# leds_vaga.net
KiCad netlist of a schematic drawn in Altium Designer
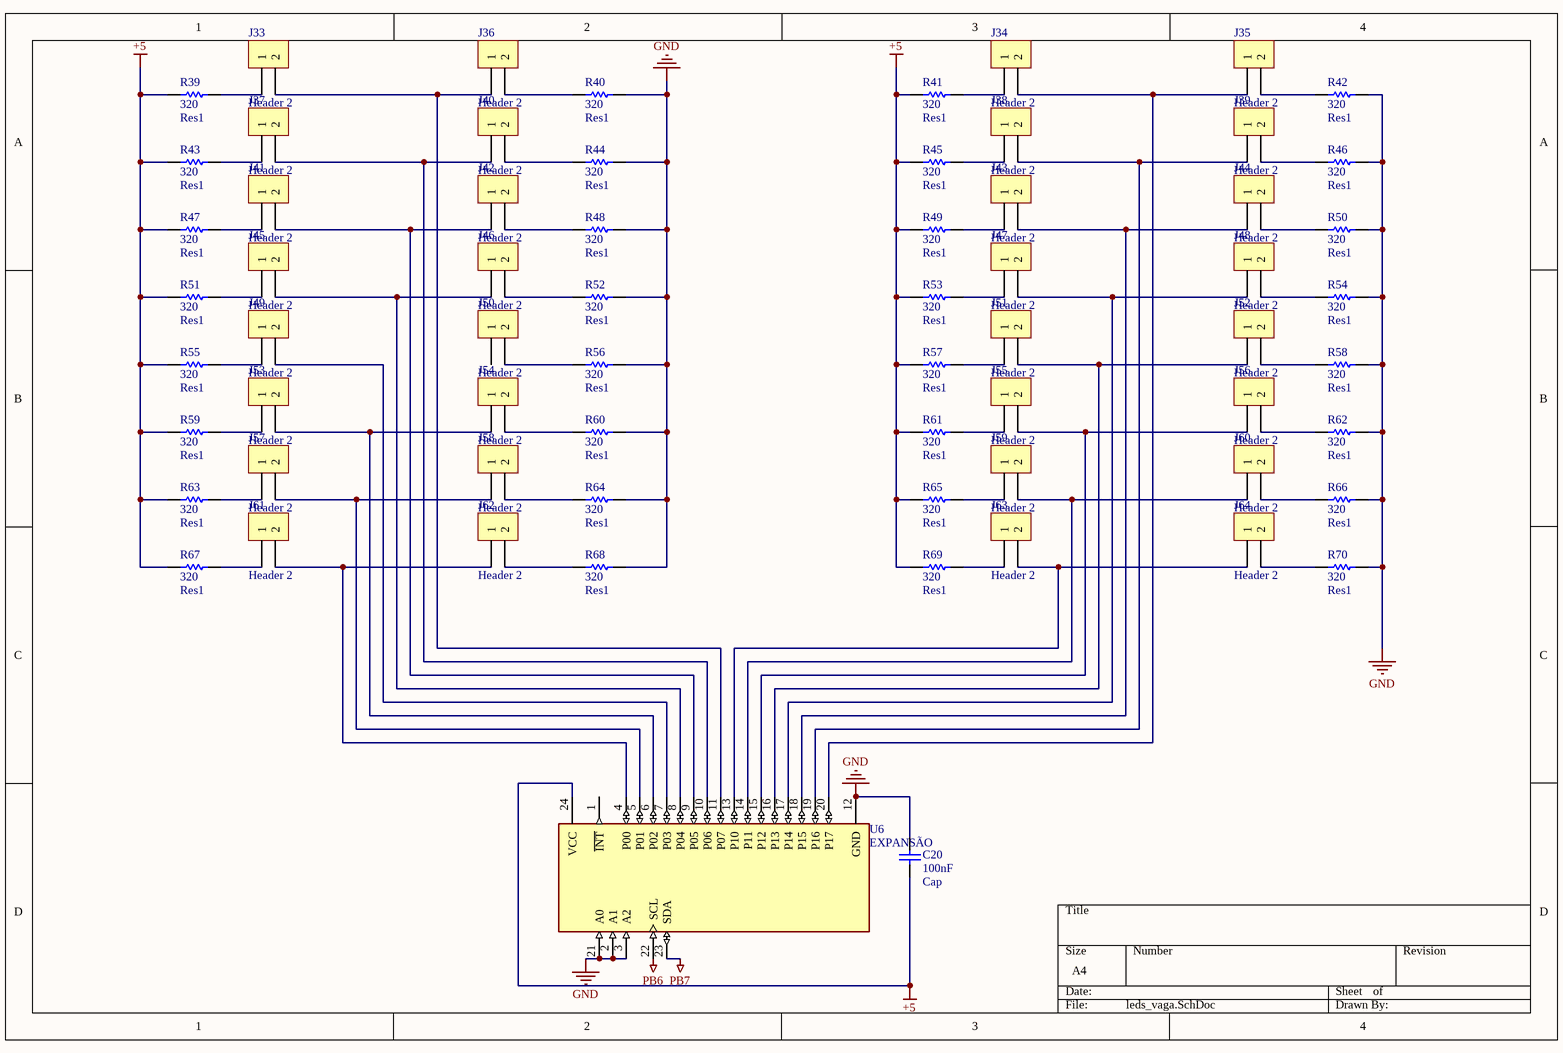
[diagram p0: leds_vaga.SchDoc]

(export (version "E")
  (design (tool "Eeschema 10.0.6"))
  (components
    (comp (ref "C20")
      (value "Cap")
      (footprint "lib_footprint_projeto:CAP100N")
      (description "Capacitor")
      (fields (field (name "ALTIUM_VALUE") "100nF") (field (name "PUBLISHER") "Altium Limited"))
      (libsource (lib "Miscellaneous Devices") (part "Cap"))
    )
    (comp (ref "J33")
      (value "Header 2")
      (footprint "lib_footprint_projeto:Header_KK_2vias")
      (description "Conn KK 2 vias")
      (fields (field (name "PUBLISHER") "Altium Limited"))
      (libsource (lib "projeto_pi_3b") (part "Header 2"))
    )
    (comp (ref "J34")
      (value "Header 2")
      (footprint "lib_footprint_projeto:Header_KK_2vias")
      (description "Conn KK 2 vias")
      (fields (field (name "PUBLISHER") "Altium Limited"))
      (libsource (lib "projeto_pi_3b") (part "Header 2"))
    )
    (comp (ref "J35")
      (value "Header 2")
      (footprint "lib_footprint_projeto:Header_KK_2vias")
      (description "Conn KK 2 vias")
      (fields (field (name "PUBLISHER") "Altium Limited"))
      (libsource (lib "projeto_pi_3b") (part "Header 2"))
    )
    (comp (ref "J36")
      (value "Header 2")
      (footprint "lib_footprint_projeto:Header_KK_2vias")
      (description "Conn KK 2 vias")
      (fields (field (name "PUBLISHER") "Altium Limited"))
      (libsource (lib "projeto_pi_3b") (part "Header 2"))
    )
    (comp (ref "J37")
      (value "Header 2")
      (footprint "lib_footprint_projeto:Header_KK_2vias")
      (description "Conn KK 2 vias")
      (fields (field (name "PUBLISHER") "Altium Limited"))
      (libsource (lib "projeto_pi_3b") (part "Header 2"))
    )
    (comp (ref "J38")
      (value "Header 2")
      (footprint "lib_footprint_projeto:Header_KK_2vias")
      (description "Conn KK 2 vias")
      (fields (field (name "PUBLISHER") "Altium Limited"))
      (libsource (lib "projeto_pi_3b") (part "Header 2"))
    )
    (comp (ref "J39")
      (value "Header 2")
      (footprint "lib_footprint_projeto:Header_KK_2vias")
      (description "Conn KK 2 vias")
      (fields (field (name "PUBLISHER") "Altium Limited"))
      (libsource (lib "projeto_pi_3b") (part "Header 2"))
    )
    (comp (ref "J40")
      (value "Header 2")
      (footprint "Header_KK_2vias")
      (description "Conn KK 2 vias")
      (fields (field (name "PUBLISHER") "Altium Limited"))
      (libsource (lib "projeto_pi_3b") (part "Header 2"))
    )
    (comp (ref "J41")
      (value "Header 2")
      (footprint "lib_footprint_projeto:Header_KK_2vias")
      (description "Conn KK 2 vias")
      (fields (field (name "PUBLISHER") "Altium Limited"))
      (libsource (lib "projeto_pi_3b") (part "Header 2"))
    )
    (comp (ref "J42")
      (value "Header 2")
      (footprint "lib_footprint_projeto:Header_KK_2vias")
      (description "Conn KK 2 vias")
      (fields (field (name "PUBLISHER") "Altium Limited"))
      (libsource (lib "projeto_pi_3b") (part "Header 2"))
    )
    (comp (ref "J43")
      (value "Header 2")
      (footprint "lib_footprint_projeto:Header_KK_2vias")
      (description "Conn KK 2 vias")
      (fields (field (name "PUBLISHER") "Altium Limited"))
      (libsource (lib "projeto_pi_3b") (part "Header 2"))
    )
    (comp (ref "J44")
      (value "Header 2")
      (footprint "lib_footprint_projeto:Header_KK_2vias")
      (description "Conn KK 2 vias")
      (fields (field (name "PUBLISHER") "Altium Limited"))
      (libsource (lib "projeto_pi_3b") (part "Header 2"))
    )
    (comp (ref "J45")
      (value "Header 2")
      (footprint "lib_footprint_projeto:Header_KK_2vias")
      (description "Conn KK 2 vias")
      (fields (field (name "PUBLISHER") "Altium Limited"))
      (libsource (lib "projeto_pi_3b") (part "Header 2"))
    )
    (comp (ref "J46")
      (value "Header 2")
      (footprint "lib_footprint_projeto:Header_KK_2vias")
      (description "Conn KK 2 vias")
      (fields (field (name "PUBLISHER") "Altium Limited"))
      (libsource (lib "projeto_pi_3b") (part "Header 2"))
    )
    (comp (ref "J47")
      (value "Header 2")
      (footprint "lib_footprint_projeto:Header_KK_2vias")
      (description "Conn KK 2 vias")
      (fields (field (name "PUBLISHER") "Altium Limited"))
      (libsource (lib "projeto_pi_3b") (part "Header 2"))
    )
    (comp (ref "J48")
      (value "Header 2")
      (footprint "lib_footprint_projeto:Header_KK_2vias")
      (description "Conn KK 2 vias")
      (fields (field (name "PUBLISHER") "Altium Limited"))
      (libsource (lib "projeto_pi_3b") (part "Header 2"))
    )
    (comp (ref "J49")
      (value "Header 2")
      (footprint "lib_footprint_projeto:Header_KK_2vias")
      (description "Conn KK 2 vias")
      (fields (field (name "PUBLISHER") "Altium Limited"))
      (libsource (lib "projeto_pi_3b") (part "Header 2"))
    )
    (comp (ref "J50")
      (value "Header 2")
      (footprint "lib_footprint_projeto:Header_KK_2vias")
      (description "Conn KK 2 vias")
      (fields (field (name "PUBLISHER") "Altium Limited"))
      (libsource (lib "projeto_pi_3b") (part "Header 2"))
    )
    (comp (ref "J51")
      (value "Header 2")
      (footprint "lib_footprint_projeto:Header_KK_2vias")
      (description "Conn KK 2 vias")
      (fields (field (name "PUBLISHER") "Altium Limited"))
      (libsource (lib "projeto_pi_3b") (part "Header 2"))
    )
    (comp (ref "J52")
      (value "Header 2")
      (footprint "lib_footprint_projeto:Header_KK_2vias")
      (description "Conn KK 2 vias")
      (fields (field (name "PUBLISHER") "Altium Limited"))
      (libsource (lib "projeto_pi_3b") (part "Header 2"))
    )
    (comp (ref "J53")
      (value "Header 2")
      (footprint "lib_footprint_projeto:Header_KK_2vias")
      (description "Conn KK 2 vias")
      (fields (field (name "PUBLISHER") "Altium Limited"))
      (libsource (lib "projeto_pi_3b") (part "Header 2"))
    )
    (comp (ref "J54")
      (value "Header 2")
      (footprint "lib_footprint_projeto:Header_KK_2vias")
      (description "Conn KK 2 vias")
      (fields (field (name "PUBLISHER") "Altium Limited"))
      (libsource (lib "projeto_pi_3b") (part "Header 2"))
    )
    (comp (ref "J55")
      (value "Header 2")
      (footprint "lib_footprint_projeto:Header_KK_2vias")
      (description "Conn KK 2 vias")
      (fields (field (name "PUBLISHER") "Altium Limited"))
      (libsource (lib "projeto_pi_3b") (part "Header 2"))
    )
    (comp (ref "J56")
      (value "Header 2")
      (footprint "lib_footprint_projeto:Header_KK_2vias")
      (description "Conn KK 2 vias")
      (fields (field (name "PUBLISHER") "Altium Limited"))
      (libsource (lib "projeto_pi_3b") (part "Header 2"))
    )
    (comp (ref "J57")
      (value "Header 2")
      (footprint "lib_footprint_projeto:Header_KK_2vias")
      (description "Conn KK 2 vias")
      (fields (field (name "PUBLISHER") "Altium Limited"))
      (libsource (lib "projeto_pi_3b") (part "Header 2"))
    )
    (comp (ref "J58")
      (value "Header 2")
      (footprint "lib_footprint_projeto:Header_KK_2vias")
      (description "Conn KK 2 vias")
      (fields (field (name "PUBLISHER") "Altium Limited"))
      (libsource (lib "projeto_pi_3b") (part "Header 2"))
    )
    (comp (ref "J59")
      (value "Header 2")
      (footprint "lib_footprint_projeto:Header_KK_2vias")
      (description "Conn KK 2 vias")
      (fields (field (name "PUBLISHER") "Altium Limited"))
      (libsource (lib "projeto_pi_3b") (part "Header 2"))
    )
    (comp (ref "J60")
      (value "Header 2")
      (footprint "lib_footprint_projeto:Header_KK_2vias")
      (description "Conn KK 2 vias")
      (fields (field (name "PUBLISHER") "Altium Limited"))
      (libsource (lib "projeto_pi_3b") (part "Header 2"))
    )
    (comp (ref "J61")
      (value "Header 2")
      (footprint "lib_footprint_projeto:Header_KK_2vias")
      (description "Conn KK 2 vias")
      (fields (field (name "PUBLISHER") "Altium Limited"))
      (libsource (lib "projeto_pi_3b") (part "Header 2"))
    )
    (comp (ref "J62")
      (value "Header 2")
      (footprint "lib_footprint_projeto:Header_KK_2vias")
      (description "Conn KK 2 vias")
      (fields (field (name "PUBLISHER") "Altium Limited"))
      (libsource (lib "projeto_pi_3b") (part "Header 2"))
    )
    (comp (ref "J63")
      (value "Header 2")
      (footprint "lib_footprint_projeto:Header_KK_2vias")
      (description "Conn KK 2 vias")
      (fields (field (name "PUBLISHER") "Altium Limited"))
      (libsource (lib "projeto_pi_3b") (part "Header 2"))
    )
    (comp (ref "J64")
      (value "Header 2")
      (footprint "lib_footprint_projeto:Header_KK_2vias")
      (description "Conn KK 2 vias")
      (fields (field (name "PUBLISHER") "Altium Limited"))
      (libsource (lib "projeto_pi_3b") (part "Header 2"))
    )
    (comp (ref "R39")
      (value "Res1")
      (footprint "lib_footprint_projeto:RES320")
      (description "Resistor")
      (fields (field (name "ALTIUM_VALUE") "320") (field (name "PUBLISHER") "Altium Limited"))
      (libsource (lib "Miscellaneous Devices") (part "Res1"))
    )
    (comp (ref "R40")
      (value "Res1")
      (footprint "lib_footprint_projeto:RES320")
      (description "Resistor")
      (fields (field (name "ALTIUM_VALUE") "320") (field (name "PUBLISHER") "Altium Limited"))
      (libsource (lib "Miscellaneous Devices") (part "Res1"))
    )
    (comp (ref "R41")
      (value "Res1")
      (footprint "lib_footprint_projeto:RES320")
      (description "Resistor")
      (fields (field (name "ALTIUM_VALUE") "320") (field (name "PUBLISHER") "Altium Limited"))
      (libsource (lib "Miscellaneous Devices") (part "Res1"))
    )
    (comp (ref "R42")
      (value "Res1")
      (footprint "lib_footprint_projeto:RES320")
      (description "Resistor")
      (fields (field (name "ALTIUM_VALUE") "320") (field (name "PUBLISHER") "Altium Limited"))
      (libsource (lib "Miscellaneous Devices") (part "Res1"))
    )
    (comp (ref "R43")
      (value "Res1")
      (footprint "lib_footprint_projeto:RES320")
      (description "Resistor")
      (fields (field (name "ALTIUM_VALUE") "320") (field (name "PUBLISHER") "Altium Limited"))
      (libsource (lib "Miscellaneous Devices") (part "Res1"))
    )
    (comp (ref "R44")
      (value "Res1")
      (footprint "lib_footprint_projeto:RES320")
      (description "Resistor")
      (fields (field (name "ALTIUM_VALUE") "320") (field (name "PUBLISHER") "Altium Limited"))
      (libsource (lib "Miscellaneous Devices") (part "Res1"))
    )
    (comp (ref "R45")
      (value "Res1")
      (footprint "lib_footprint_projeto:RES320")
      (description "Resistor")
      (fields (field (name "ALTIUM_VALUE") "320") (field (name "PUBLISHER") "Altium Limited"))
      (libsource (lib "Miscellaneous Devices") (part "Res1"))
    )
    (comp (ref "R46")
      (value "Res1")
      (footprint "lib_footprint_projeto:RES320")
      (description "Resistor")
      (fields (field (name "ALTIUM_VALUE") "320") (field (name "PUBLISHER") "Altium Limited"))
      (libsource (lib "Miscellaneous Devices") (part "Res1"))
    )
    (comp (ref "R47")
      (value "Res1")
      (footprint "lib_footprint_projeto:RES320")
      (description "Resistor")
      (fields (field (name "ALTIUM_VALUE") "320") (field (name "PUBLISHER") "Altium Limited"))
      (libsource (lib "Miscellaneous Devices") (part "Res1"))
    )
    (comp (ref "R48")
      (value "Res1")
      (footprint "lib_footprint_projeto:RES320")
      (description "Resistor")
      (fields (field (name "ALTIUM_VALUE") "320") (field (name "PUBLISHER") "Altium Limited"))
      (libsource (lib "Miscellaneous Devices") (part "Res1"))
    )
    (comp (ref "R49")
      (value "Res1")
      (footprint "lib_footprint_projeto:RES320")
      (description "Resistor")
      (fields (field (name "ALTIUM_VALUE") "320") (field (name "PUBLISHER") "Altium Limited"))
      (libsource (lib "Miscellaneous Devices") (part "Res1"))
    )
    (comp (ref "R50")
      (value "Res1")
      (footprint "lib_footprint_projeto:RES320")
      (description "Resistor")
      (fields (field (name "ALTIUM_VALUE") "320") (field (name "PUBLISHER") "Altium Limited"))
      (libsource (lib "Miscellaneous Devices") (part "Res1"))
    )
    (comp (ref "R51")
      (value "Res1")
      (footprint "lib_footprint_projeto:RES320")
      (description "Resistor")
      (fields (field (name "ALTIUM_VALUE") "320") (field (name "PUBLISHER") "Altium Limited"))
      (libsource (lib "Miscellaneous Devices") (part "Res1"))
    )
    (comp (ref "R52")
      (value "Res1")
      (footprint "lib_footprint_projeto:RES320")
      (description "Resistor")
      (fields (field (name "ALTIUM_VALUE") "320") (field (name "PUBLISHER") "Altium Limited"))
      (libsource (lib "Miscellaneous Devices") (part "Res1"))
    )
    (comp (ref "R53")
      (value "Res1")
      (footprint "lib_footprint_projeto:RES320")
      (description "Resistor")
      (fields (field (name "ALTIUM_VALUE") "320") (field (name "PUBLISHER") "Altium Limited"))
      (libsource (lib "Miscellaneous Devices") (part "Res1"))
    )
    (comp (ref "R54")
      (value "Res1")
      (footprint "lib_footprint_projeto:RES320")
      (description "Resistor")
      (fields (field (name "ALTIUM_VALUE") "320") (field (name "PUBLISHER") "Altium Limited"))
      (libsource (lib "Miscellaneous Devices") (part "Res1"))
    )
    (comp (ref "R55")
      (value "Res1")
      (footprint "lib_footprint_projeto:RES320")
      (description "Resistor")
      (fields (field (name "ALTIUM_VALUE") "320") (field (name "PUBLISHER") "Altium Limited"))
      (libsource (lib "Miscellaneous Devices") (part "Res1"))
    )
    (comp (ref "R56")
      (value "Res1")
      (footprint "lib_footprint_projeto:RES320")
      (description "Resistor")
      (fields (field (name "ALTIUM_VALUE") "320") (field (name "PUBLISHER") "Altium Limited"))
      (libsource (lib "Miscellaneous Devices") (part "Res1"))
    )
    (comp (ref "R57")
      (value "Res1")
      (footprint "lib_footprint_projeto:RES320")
      (description "Resistor")
      (fields (field (name "ALTIUM_VALUE") "320") (field (name "PUBLISHER") "Altium Limited"))
      (libsource (lib "Miscellaneous Devices") (part "Res1"))
    )
    (comp (ref "R58")
      (value "Res1")
      (footprint "lib_footprint_projeto:RES320")
      (description "Resistor")
      (fields (field (name "ALTIUM_VALUE") "320") (field (name "PUBLISHER") "Altium Limited"))
      (libsource (lib "Miscellaneous Devices") (part "Res1"))
    )
    (comp (ref "R59")
      (value "Res1")
      (footprint "lib_footprint_projeto:RES320")
      (description "Resistor")
      (fields (field (name "ALTIUM_VALUE") "320") (field (name "PUBLISHER") "Altium Limited"))
      (libsource (lib "Miscellaneous Devices") (part "Res1"))
    )
    (comp (ref "R60")
      (value "Res1")
      (footprint "lib_footprint_projeto:RES320")
      (description "Resistor")
      (fields (field (name "ALTIUM_VALUE") "320") (field (name "PUBLISHER") "Altium Limited"))
      (libsource (lib "Miscellaneous Devices") (part "Res1"))
    )
    (comp (ref "R61")
      (value "Res1")
      (footprint "lib_footprint_projeto:RES320")
      (description "Resistor")
      (fields (field (name "ALTIUM_VALUE") "320") (field (name "PUBLISHER") "Altium Limited"))
      (libsource (lib "Miscellaneous Devices") (part "Res1"))
    )
    (comp (ref "R62")
      (value "Res1")
      (footprint "lib_footprint_projeto:RES320")
      (description "Resistor")
      (fields (field (name "ALTIUM_VALUE") "320") (field (name "PUBLISHER") "Altium Limited"))
      (libsource (lib "Miscellaneous Devices") (part "Res1"))
    )
    (comp (ref "R63")
      (value "Res1")
      (footprint "lib_footprint_projeto:RES320")
      (description "Resistor")
      (fields (field (name "ALTIUM_VALUE") "320") (field (name "PUBLISHER") "Altium Limited"))
      (libsource (lib "Miscellaneous Devices") (part "Res1"))
    )
    (comp (ref "R64")
      (value "Res1")
      (footprint "lib_footprint_projeto:RES320")
      (description "Resistor")
      (fields (field (name "ALTIUM_VALUE") "320") (field (name "PUBLISHER") "Altium Limited"))
      (libsource (lib "Miscellaneous Devices") (part "Res1"))
    )
    (comp (ref "R65")
      (value "Res1")
      (footprint "lib_footprint_projeto:RES320")
      (description "Resistor")
      (fields (field (name "ALTIUM_VALUE") "320") (field (name "PUBLISHER") "Altium Limited"))
      (libsource (lib "Miscellaneous Devices") (part "Res1"))
    )
    (comp (ref "R66")
      (value "Res1")
      (footprint "lib_footprint_projeto:RES320")
      (description "Resistor")
      (fields (field (name "ALTIUM_VALUE") "320") (field (name "PUBLISHER") "Altium Limited"))
      (libsource (lib "Miscellaneous Devices") (part "Res1"))
    )
    (comp (ref "R67")
      (value "Res1")
      (footprint "lib_footprint_projeto:RES320")
      (description "Resistor")
      (fields (field (name "ALTIUM_VALUE") "320") (field (name "PUBLISHER") "Altium Limited"))
      (libsource (lib "Miscellaneous Devices") (part "Res1"))
    )
    (comp (ref "R68")
      (value "Res1")
      (footprint "lib_footprint_projeto:RES320")
      (description "Resistor")
      (fields (field (name "ALTIUM_VALUE") "320") (field (name "PUBLISHER") "Altium Limited"))
      (libsource (lib "Miscellaneous Devices") (part "Res1"))
    )
    (comp (ref "R69")
      (value "Res1")
      (footprint "lib_footprint_projeto:RES320")
      (description "Resistor")
      (fields (field (name "ALTIUM_VALUE") "320") (field (name "PUBLISHER") "Altium Limited"))
      (libsource (lib "Miscellaneous Devices") (part "Res1"))
    )
    (comp (ref "R70")
      (value "Res1")
      (footprint "lib_footprint_projeto:RES320")
      (description "Resistor")
      (fields (field (name "ALTIUM_VALUE") "320") (field (name "PUBLISHER") "Altium Limited"))
      (libsource (lib "Miscellaneous Devices") (part "Res1"))
    )
    (comp (ref "U6")
      (value "EXPANSÃO")
      (footprint "lib_footprint_projeto:Modulo")
      (description "16-bit 2.5- to 5.5-V I2C/SMBus I/O expander with interrupt")
      (fields (field (name "MF") "Texas Instruments") (field (name "MP") "PCF8575DW"))
      (libsource (lib "projeto_pi_3b") (part "EXPANSÃO"))
    )
  )
  (nets
    (net (code "1") (name "+5") (class "Default")
      (node (ref "C20") (pin "1") (pinfunction "1_1") (pintype "passive"))
      (node (ref "R39") (pin "1") (pinfunction "1_1") (pintype "passive"))
      (node (ref "R41") (pin "1") (pinfunction "1_1") (pintype "passive"))
      (node (ref "R43") (pin "1") (pinfunction "1_1") (pintype "passive"))
      (node (ref "R45") (pin "1") (pinfunction "1_1") (pintype "passive"))
      (node (ref "R47") (pin "1") (pinfunction "1_1") (pintype "passive"))
      (node (ref "R49") (pin "1") (pinfunction "1_1") (pintype "passive"))
      (node (ref "R51") (pin "1") (pinfunction "1_1") (pintype "passive"))
      (node (ref "R53") (pin "1") (pinfunction "1_1") (pintype "passive"))
      (node (ref "R55") (pin "1") (pinfunction "1_1") (pintype "passive"))
      (node (ref "R57") (pin "1") (pinfunction "1_1") (pintype "passive"))
      (node (ref "R59") (pin "1") (pinfunction "1_1") (pintype "passive"))
      (node (ref "R61") (pin "1") (pinfunction "1_1") (pintype "passive"))
      (node (ref "R63") (pin "1") (pinfunction "1_1") (pintype "passive"))
      (node (ref "R65") (pin "1") (pinfunction "1_1") (pintype "passive"))
      (node (ref "R67") (pin "1") (pinfunction "1_1") (pintype "passive"))
      (node (ref "R69") (pin "1") (pinfunction "1_1") (pintype "passive"))
      (node (ref "U6") (pin "24") (pinfunction "VCC_24") (pintype "power_in"))
    )
    (net (code "2") (name "GND") (class "Default")
      (node (ref "C20") (pin "2") (pinfunction "2_2") (pintype "passive"))
      (node (ref "R40") (pin "2") (pinfunction "2_2") (pintype "passive"))
      (node (ref "R42") (pin "2") (pinfunction "2_2") (pintype "passive"))
      (node (ref "R44") (pin "2") (pinfunction "2_2") (pintype "passive"))
      (node (ref "R46") (pin "2") (pinfunction "2_2") (pintype "passive"))
      (node (ref "R48") (pin "2") (pinfunction "2_2") (pintype "passive"))
      (node (ref "R50") (pin "2") (pinfunction "2_2") (pintype "passive"))
      (node (ref "R52") (pin "2") (pinfunction "2_2") (pintype "passive"))
      (node (ref "R54") (pin "2") (pinfunction "2_2") (pintype "passive"))
      (node (ref "R56") (pin "2") (pinfunction "2_2") (pintype "passive"))
      (node (ref "R58") (pin "2") (pinfunction "2_2") (pintype "passive"))
      (node (ref "R60") (pin "2") (pinfunction "2_2") (pintype "passive"))
      (node (ref "R62") (pin "2") (pinfunction "2_2") (pintype "passive"))
      (node (ref "R64") (pin "2") (pinfunction "2_2") (pintype "passive"))
      (node (ref "R66") (pin "2") (pinfunction "2_2") (pintype "passive"))
      (node (ref "R68") (pin "2") (pinfunction "2_2") (pintype "passive"))
      (node (ref "R70") (pin "2") (pinfunction "2_2") (pintype "passive"))
      (node (ref "U6") (pin "12") (pinfunction "GND_12") (pintype "power_in"))
      (node (ref "U6") (pin "2") (pinfunction "A1_2") (pintype "input"))
      (node (ref "U6") (pin "21") (pinfunction "A0_21") (pintype "input"))
      (node (ref "U6") (pin "3") (pinfunction "A2_3") (pintype "input"))
    )
    (net (code "3") (name "Net-(J33-Pad1)") (class "Default")
      (node (ref "J33") (pin "1") (pinfunction "1_1") (pintype "passive"))
      (node (ref "R39") (pin "2") (pinfunction "2_2") (pintype "passive"))
    )
    (net (code "4") (name "Net-(J34-Pad1)") (class "Default")
      (node (ref "J34") (pin "1") (pinfunction "1_1") (pintype "passive"))
      (node (ref "R41") (pin "2") (pinfunction "2_2") (pintype "passive"))
    )
    (net (code "5") (name "Net-(J35-Pad2)") (class "Default")
      (node (ref "J35") (pin "2") (pinfunction "2_2") (pintype "passive"))
      (node (ref "R42") (pin "1") (pinfunction "1_1") (pintype "passive"))
    )
    (net (code "6") (name "Net-(J36-Pad2)") (class "Default")
      (node (ref "J36") (pin "2") (pinfunction "2_2") (pintype "passive"))
      (node (ref "R40") (pin "1") (pinfunction "1_1") (pintype "passive"))
    )
    (net (code "7") (name "Net-(J37-Pad1)") (class "Default")
      (node (ref "J37") (pin "1") (pinfunction "1_1") (pintype "passive"))
      (node (ref "R43") (pin "2") (pinfunction "2_2") (pintype "passive"))
    )
    (net (code "8") (name "Net-(J38-Pad1)") (class "Default")
      (node (ref "J38") (pin "1") (pinfunction "1_1") (pintype "passive"))
      (node (ref "R45") (pin "2") (pinfunction "2_2") (pintype "passive"))
    )
    (net (code "9") (name "Net-(J39-Pad2)") (class "Default")
      (node (ref "J39") (pin "2") (pinfunction "2_2") (pintype "passive"))
      (node (ref "R46") (pin "1") (pinfunction "1_1") (pintype "passive"))
    )
    (net (code "10") (name "Net-(J40-Pad2)") (class "Default")
      (node (ref "J40") (pin "2") (pinfunction "2_2") (pintype "passive"))
      (node (ref "R44") (pin "1") (pinfunction "1_1") (pintype "passive"))
    )
    (net (code "11") (name "Net-(J41-Pad1)") (class "Default")
      (node (ref "J41") (pin "1") (pinfunction "1_1") (pintype "passive"))
      (node (ref "R47") (pin "2") (pinfunction "2_2") (pintype "passive"))
    )
    (net (code "12") (name "Net-(J42-Pad2)") (class "Default")
      (node (ref "J42") (pin "2") (pinfunction "2_2") (pintype "passive"))
      (node (ref "R48") (pin "1") (pinfunction "1_1") (pintype "passive"))
    )
    (net (code "13") (name "Net-(J43-Pad1)") (class "Default")
      (node (ref "J43") (pin "1") (pinfunction "1_1") (pintype "passive"))
      (node (ref "R49") (pin "2") (pinfunction "2_2") (pintype "passive"))
    )
    (net (code "14") (name "Net-(J44-Pad2)") (class "Default")
      (node (ref "J44") (pin "2") (pinfunction "2_2") (pintype "passive"))
      (node (ref "R50") (pin "1") (pinfunction "1_1") (pintype "passive"))
    )
    (net (code "15") (name "Net-(J45-Pad1)") (class "Default")
      (node (ref "J45") (pin "1") (pinfunction "1_1") (pintype "passive"))
      (node (ref "R51") (pin "2") (pinfunction "2_2") (pintype "passive"))
    )
    (net (code "16") (name "Net-(J46-Pad2)") (class "Default")
      (node (ref "J46") (pin "2") (pinfunction "2_2") (pintype "passive"))
      (node (ref "R52") (pin "1") (pinfunction "1_1") (pintype "passive"))
    )
    (net (code "17") (name "Net-(J47-Pad1)") (class "Default")
      (node (ref "J47") (pin "1") (pinfunction "1_1") (pintype "passive"))
      (node (ref "R53") (pin "2") (pinfunction "2_2") (pintype "passive"))
    )
    (net (code "18") (name "Net-(J48-Pad2)") (class "Default")
      (node (ref "J48") (pin "2") (pinfunction "2_2") (pintype "passive"))
      (node (ref "R54") (pin "1") (pinfunction "1_1") (pintype "passive"))
    )
    (net (code "19") (name "Net-(J49-Pad1)") (class "Default")
      (node (ref "J49") (pin "1") (pinfunction "1_1") (pintype "passive"))
      (node (ref "R55") (pin "2") (pinfunction "2_2") (pintype "passive"))
    )
    (net (code "20") (name "Net-(J50-Pad2)") (class "Default")
      (node (ref "J50") (pin "2") (pinfunction "2_2") (pintype "passive"))
      (node (ref "R56") (pin "1") (pinfunction "1_1") (pintype "passive"))
    )
    (net (code "21") (name "Net-(J51-Pad1)") (class "Default")
      (node (ref "J51") (pin "1") (pinfunction "1_1") (pintype "passive"))
      (node (ref "R57") (pin "2") (pinfunction "2_2") (pintype "passive"))
    )
    (net (code "22") (name "Net-(J52-Pad2)") (class "Default")
      (node (ref "J52") (pin "2") (pinfunction "2_2") (pintype "passive"))
      (node (ref "R58") (pin "1") (pinfunction "1_1") (pintype "passive"))
    )
    (net (code "23") (name "Net-(J53-Pad1)") (class "Default")
      (node (ref "J53") (pin "1") (pinfunction "1_1") (pintype "passive"))
      (node (ref "R59") (pin "2") (pinfunction "2_2") (pintype "passive"))
    )
    (net (code "24") (name "Net-(J54-Pad2)") (class "Default")
      (node (ref "J54") (pin "2") (pinfunction "2_2") (pintype "passive"))
      (node (ref "R60") (pin "1") (pinfunction "1_1") (pintype "passive"))
    )
    (net (code "25") (name "Net-(J55-Pad1)") (class "Default")
      (node (ref "J55") (pin "1") (pinfunction "1_1") (pintype "passive"))
      (node (ref "R61") (pin "2") (pinfunction "2_2") (pintype "passive"))
    )
    (net (code "26") (name "Net-(J56-Pad2)") (class "Default")
      (node (ref "J56") (pin "2") (pinfunction "2_2") (pintype "passive"))
      (node (ref "R62") (pin "1") (pinfunction "1_1") (pintype "passive"))
    )
    (net (code "27") (name "Net-(J57-Pad1)") (class "Default")
      (node (ref "J57") (pin "1") (pinfunction "1_1") (pintype "passive"))
      (node (ref "R63") (pin "2") (pinfunction "2_2") (pintype "passive"))
    )
    (net (code "28") (name "Net-(J58-Pad2)") (class "Default")
      (node (ref "J58") (pin "2") (pinfunction "2_2") (pintype "passive"))
      (node (ref "R64") (pin "1") (pinfunction "1_1") (pintype "passive"))
    )
    (net (code "29") (name "Net-(J59-Pad1)") (class "Default")
      (node (ref "J59") (pin "1") (pinfunction "1_1") (pintype "passive"))
      (node (ref "R65") (pin "2") (pinfunction "2_2") (pintype "passive"))
    )
    (net (code "30") (name "Net-(J60-Pad2)") (class "Default")
      (node (ref "J60") (pin "2") (pinfunction "2_2") (pintype "passive"))
      (node (ref "R66") (pin "1") (pinfunction "1_1") (pintype "passive"))
    )
    (net (code "31") (name "Net-(J61-Pad1)") (class "Default")
      (node (ref "J61") (pin "1") (pinfunction "1_1") (pintype "passive"))
      (node (ref "R67") (pin "2") (pinfunction "2_2") (pintype "passive"))
    )
    (net (code "32") (name "Net-(J62-Pad2)") (class "Default")
      (node (ref "J62") (pin "2") (pinfunction "2_2") (pintype "passive"))
      (node (ref "R68") (pin "1") (pinfunction "1_1") (pintype "passive"))
    )
    (net (code "33") (name "Net-(J63-Pad1)") (class "Default")
      (node (ref "J63") (pin "1") (pinfunction "1_1") (pintype "passive"))
      (node (ref "R69") (pin "2") (pinfunction "2_2") (pintype "passive"))
    )
    (net (code "34") (name "Net-(J64-Pad2)") (class "Default")
      (node (ref "J64") (pin "2") (pinfunction "2_2") (pintype "passive"))
      (node (ref "R70") (pin "1") (pinfunction "1_1") (pintype "passive"))
    )
    (net (code "35") (name "Net-(U6-P00)") (class "Default")
      (node (ref "J61") (pin "2") (pinfunction "2_2") (pintype "passive"))
      (node (ref "J62") (pin "1") (pinfunction "1_1") (pintype "passive"))
      (node (ref "U6") (pin "4") (pinfunction "P00_4") (pintype "bidirectional"))
    )
    (net (code "36") (name "Net-(U6-P01)") (class "Default")
      (node (ref "J57") (pin "2") (pinfunction "2_2") (pintype "passive"))
      (node (ref "J58") (pin "1") (pinfunction "1_1") (pintype "passive"))
      (node (ref "U6") (pin "5") (pinfunction "P01_5") (pintype "bidirectional"))
    )
    (net (code "37") (name "Net-(U6-P02)") (class "Default")
      (node (ref "J53") (pin "2") (pinfunction "2_2") (pintype "passive"))
      (node (ref "J54") (pin "1") (pinfunction "1_1") (pintype "passive"))
      (node (ref "U6") (pin "6") (pinfunction "P02_6") (pintype "bidirectional"))
    )
    (net (code "38") (name "Net-(U6-P03)") (class "Default")
      (node (ref "J49") (pin "2") (pinfunction "2_2") (pintype "passive"))
      (node (ref "U6") (pin "7") (pinfunction "P03_7") (pintype "bidirectional"))
    )
    (net (code "39") (name "Net-(U6-P04)") (class "Default")
      (node (ref "J45") (pin "2") (pinfunction "2_2") (pintype "passive"))
      (node (ref "J46") (pin "1") (pinfunction "1_1") (pintype "passive"))
      (node (ref "U6") (pin "8") (pinfunction "P04_8") (pintype "bidirectional"))
    )
    (net (code "40") (name "Net-(U6-P05)") (class "Default")
      (node (ref "J41") (pin "2") (pinfunction "2_2") (pintype "passive"))
      (node (ref "J42") (pin "1") (pinfunction "1_1") (pintype "passive"))
      (node (ref "U6") (pin "9") (pinfunction "P05_9") (pintype "bidirectional"))
    )
    (net (code "41") (name "Net-(U6-P06)") (class "Default")
      (node (ref "J37") (pin "2") (pinfunction "2_2") (pintype "passive"))
      (node (ref "J40") (pin "1") (pinfunction "1_1") (pintype "passive"))
      (node (ref "U6") (pin "10") (pinfunction "P06_10") (pintype "bidirectional"))
    )
    (net (code "42") (name "Net-(U6-P07)") (class "Default")
      (node (ref "J33") (pin "2") (pinfunction "2_2") (pintype "passive"))
      (node (ref "J36") (pin "1") (pinfunction "1_1") (pintype "passive"))
      (node (ref "U6") (pin "11") (pinfunction "P07_11") (pintype "bidirectional"))
    )
    (net (code "43") (name "Net-(U6-P10)") (class "Default")
      (node (ref "J63") (pin "2") (pinfunction "2_2") (pintype "passive"))
      (node (ref "J64") (pin "1") (pinfunction "1_1") (pintype "passive"))
      (node (ref "U6") (pin "13") (pinfunction "P10_13") (pintype "bidirectional"))
    )
    (net (code "44") (name "Net-(U6-P11)") (class "Default")
      (node (ref "J59") (pin "2") (pinfunction "2_2") (pintype "passive"))
      (node (ref "J60") (pin "1") (pinfunction "1_1") (pintype "passive"))
      (node (ref "U6") (pin "14") (pinfunction "P11_14") (pintype "bidirectional"))
    )
    (net (code "45") (name "Net-(U6-P12)") (class "Default")
      (node (ref "J55") (pin "2") (pinfunction "2_2") (pintype "passive"))
      (node (ref "J56") (pin "1") (pinfunction "1_1") (pintype "passive"))
      (node (ref "U6") (pin "15") (pinfunction "P12_15") (pintype "bidirectional"))
    )
    (net (code "46") (name "Net-(U6-P13)") (class "Default")
      (node (ref "J51") (pin "2") (pinfunction "2_2") (pintype "passive"))
      (node (ref "J52") (pin "1") (pinfunction "1_1") (pintype "passive"))
      (node (ref "U6") (pin "16") (pinfunction "P13_16") (pintype "bidirectional"))
    )
    (net (code "47") (name "Net-(U6-P14)") (class "Default")
      (node (ref "J47") (pin "2") (pinfunction "2_2") (pintype "passive"))
      (node (ref "J48") (pin "1") (pinfunction "1_1") (pintype "passive"))
      (node (ref "U6") (pin "17") (pinfunction "P14_17") (pintype "bidirectional"))
    )
    (net (code "48") (name "Net-(U6-P15)") (class "Default")
      (node (ref "J43") (pin "2") (pinfunction "2_2") (pintype "passive"))
      (node (ref "J44") (pin "1") (pinfunction "1_1") (pintype "passive"))
      (node (ref "U6") (pin "18") (pinfunction "P15_18") (pintype "bidirectional"))
    )
    (net (code "49") (name "Net-(U6-P16)") (class "Default")
      (node (ref "J38") (pin "2") (pinfunction "2_2") (pintype "passive"))
      (node (ref "J39") (pin "1") (pinfunction "1_1") (pintype "passive"))
      (node (ref "U6") (pin "19") (pinfunction "P16_19") (pintype "bidirectional"))
    )
    (net (code "50") (name "Net-(U6-P17)") (class "Default")
      (node (ref "J34") (pin "2") (pinfunction "2_2") (pintype "passive"))
      (node (ref "J35") (pin "1") (pinfunction "1_1") (pintype "passive"))
      (node (ref "U6") (pin "20") (pinfunction "P17_20") (pintype "bidirectional"))
    )
    (net (code "51") (name "PB6") (class "Default")
      (node (ref "U6") (pin "22") (pinfunction "SCL_22") (pintype "input"))
    )
    (net (code "52") (name "PB7") (class "Default")
      (node (ref "U6") (pin "23") (pinfunction "SDA_23") (pintype "bidirectional"))
    )
    (net (code "53") (name "unconnected-(J50-Pad1)") (class "Default")
      (node (ref "J50") (pin "1") (pinfunction "1_1") (pintype "passive"))
    )
    (net (code "54") (name "unconnected-(U6-~{INT}-Pad1)") (class "Default")
      (node (ref "U6") (pin "1") (pinfunction "~{INT}_1") (pintype "output"))
    )
  )
)
